# BW1098OBC_USB.net
KiCad netlist of a schematic drawn in Altium Designer
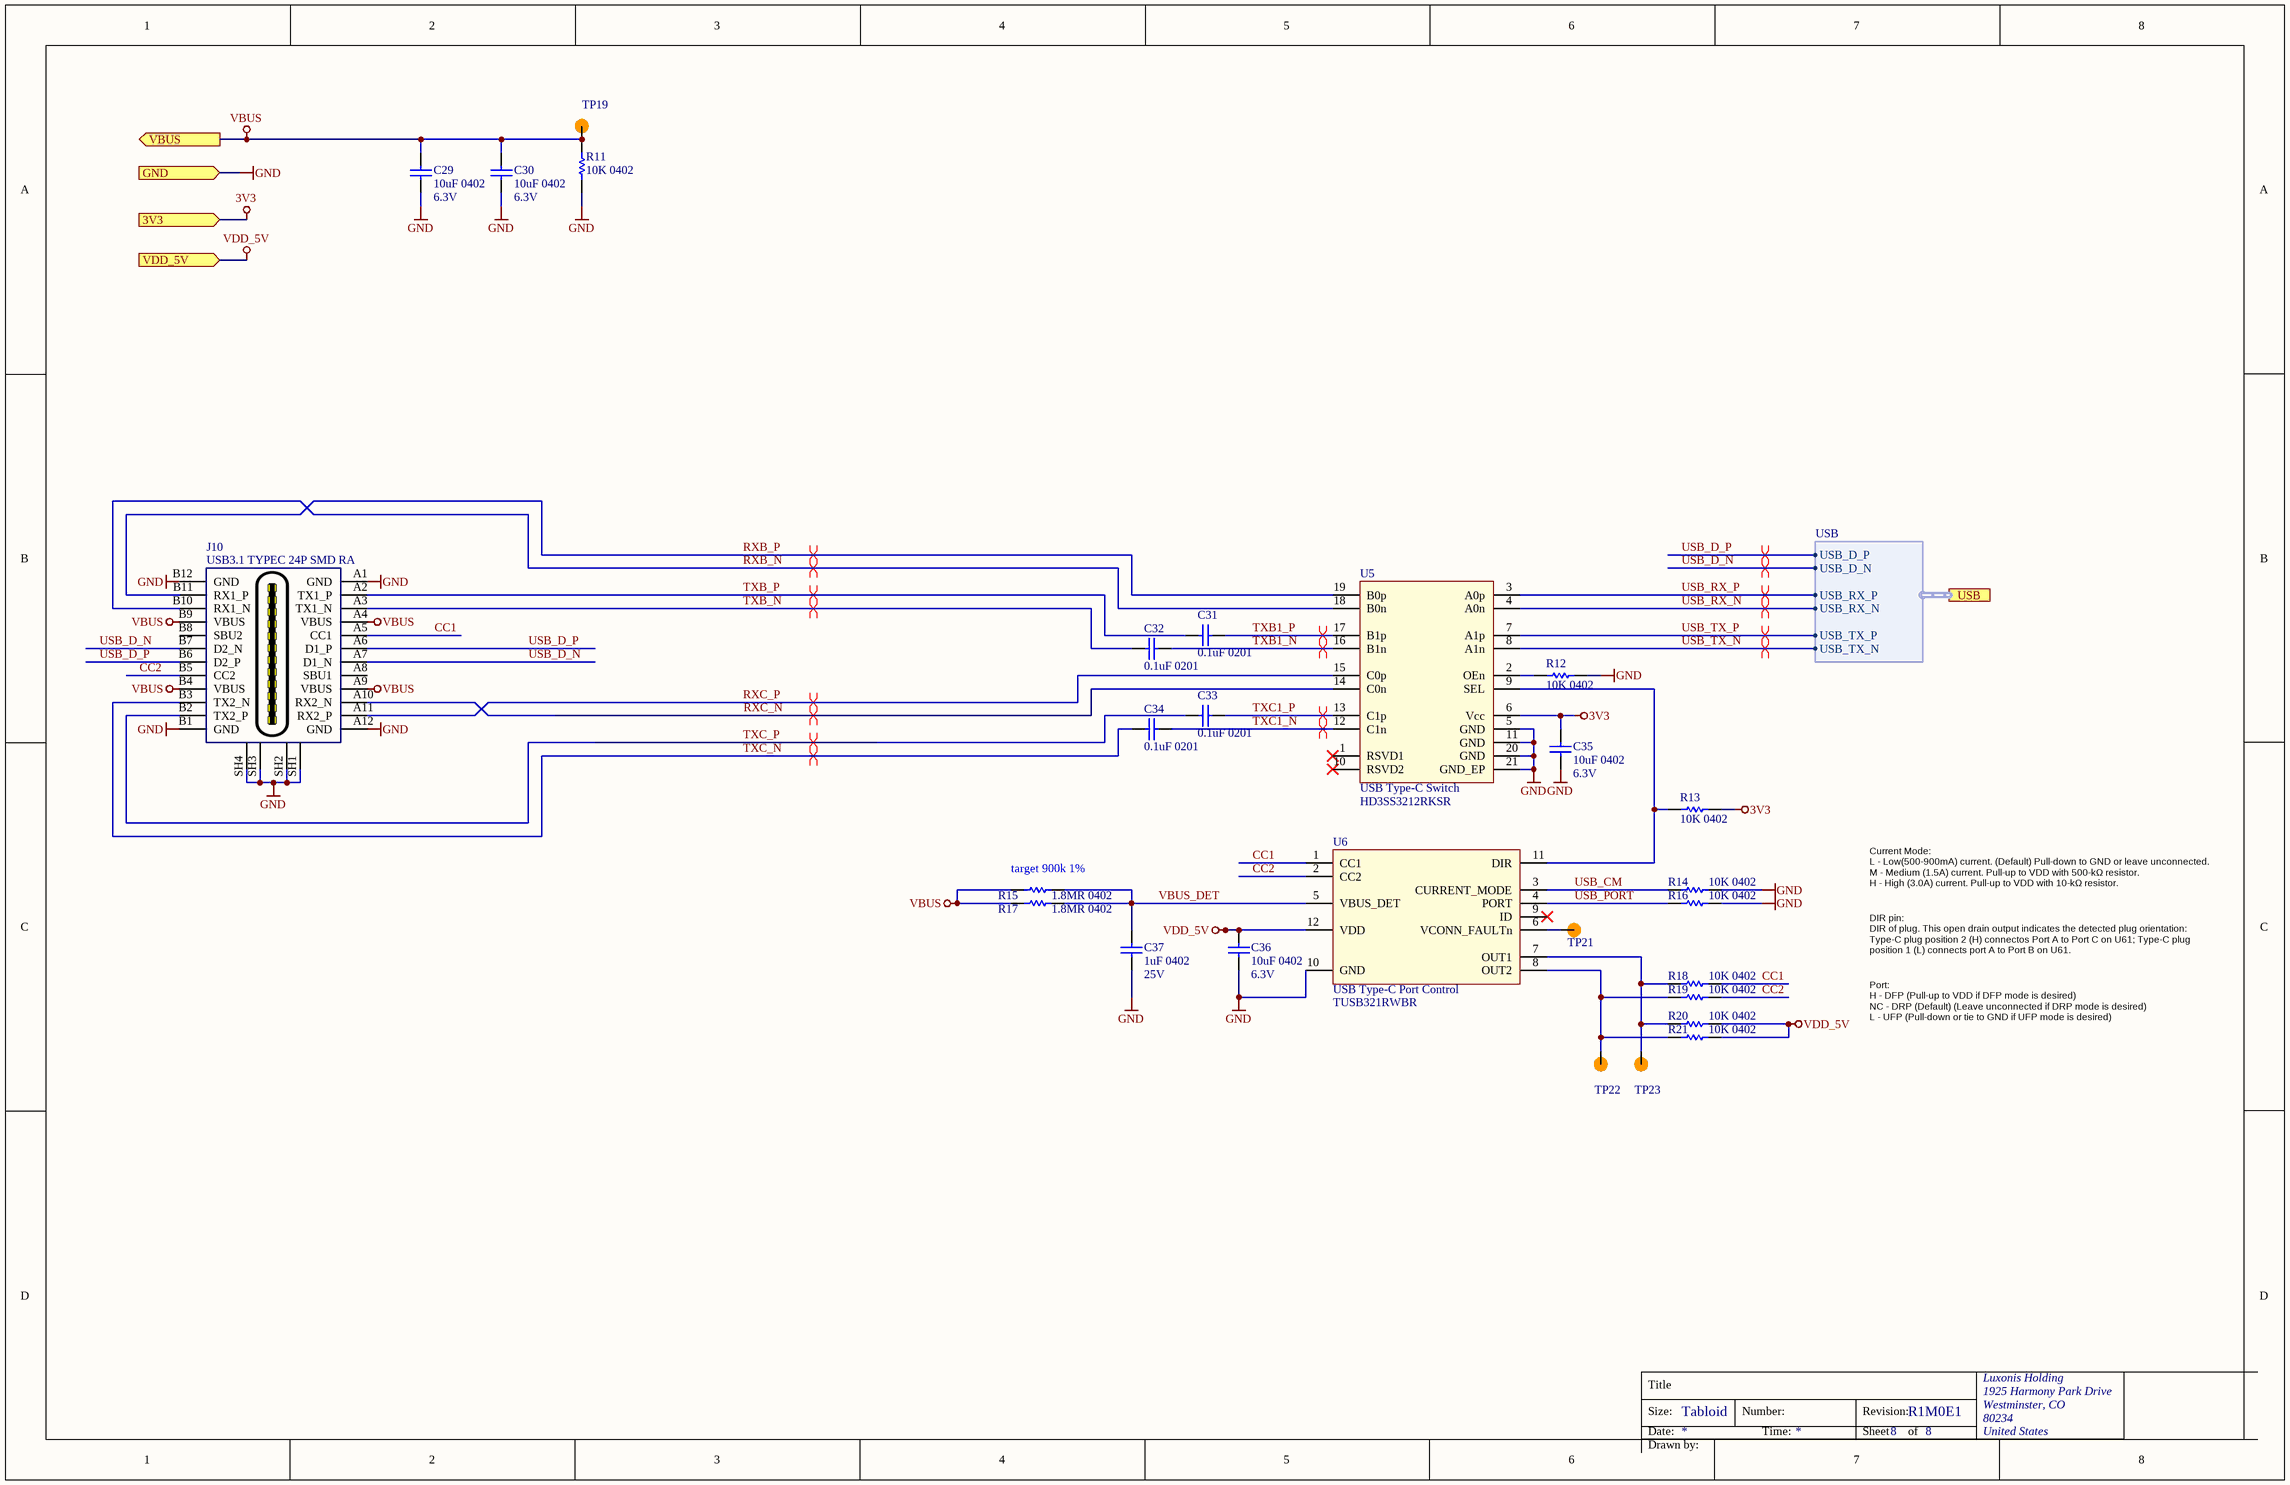
[diagram p0: BW1098OBC_USB.SchDoc]

(export (version "E")
  (design (tool "Eeschema 10.0.6"))
  (components
    (comp (ref "C29")
      (value "10uF 0402")
      (footprint "CAP_Altium_Vault_Generic:CAPC0402(1005)70_L")
      (description "CAP CER 10UF 6.3V X5R 0402 20%")
      (fields (field (name "TOLERANCE") "20%") (field (name "VOLTAGE RATING") "6.3V"))
      (libsource (lib "LuxonisMaster") (part "GRM155R60J106ME15D"))
    )
    (comp (ref "C30")
      (value "10uF 0402")
      (footprint "CAP_Altium_Vault_Generic:CAPC0402(1005)70_L")
      (description "CAP CER 10UF 6.3V X5R 0402 20%")
      (fields (field (name "TOLERANCE") "20%") (field (name "VOLTAGE RATING") "6.3V"))
      (libsource (lib "LuxonisMaster") (part "GRM155R60J106ME15D"))
    )
    (comp (ref "C31")
      (value "0.1uF 0201")
      (footprint "CAP_Altium_Vault_Generic:CAPC0201(0603)33_L")
      (description "CAP CER 0.1UF 10V X5R 0201")
      (fields (field (name "TOLERANCE") "10%") (field (name "VOLTAGE") "10V"))
      (libsource (lib "LuxonisMaster") (part "GRM033R61A104KE15D"))
    )
    (comp (ref "C32")
      (value "0.1uF 0201")
      (footprint "CAP_Altium_Vault_Generic:CAPC0201(0603)33_L")
      (description "CAP CER 0.1UF 10V X5R 0201")
      (fields (field (name "TOLERANCE") "10%") (field (name "VOLTAGE") "10V"))
      (libsource (lib "LuxonisMaster") (part "GRM033R61A104KE15D"))
    )
    (comp (ref "C33")
      (value "0.1uF 0201")
      (footprint "CAP_Altium_Vault_Generic:CAPC0201(0603)33_L")
      (description "CAP CER 0.1UF 10V X5R 0201")
      (fields (field (name "TOLERANCE") "10%") (field (name "VOLTAGE") "10V"))
      (libsource (lib "LuxonisMaster") (part "GRM033R61A104KE15D"))
    )
    (comp (ref "C34")
      (value "0.1uF 0201")
      (footprint "CAP_Altium_Vault_Generic:CAPC0201(0603)33_L")
      (description "CAP CER 0.1UF 10V X5R 0201")
      (fields (field (name "TOLERANCE") "10%") (field (name "VOLTAGE") "10V"))
      (libsource (lib "LuxonisMaster") (part "GRM033R61A104KE15D"))
    )
    (comp (ref "C35")
      (value "10uF 0402")
      (footprint "CAP_Altium_Vault_Generic:CAPC0402(1005)70_L")
      (description "CAP CER 10UF 6.3V X5R 0402 20%")
      (fields (field (name "TOLERANCE") "20%") (field (name "VOLTAGE RATING") "6.3V"))
      (libsource (lib "LuxonisMaster") (part "GRM155R60J106ME15D"))
    )
    (comp (ref "C36")
      (value "10uF 0402")
      (footprint "CAP_Altium_Vault_Generic:CAPC0402(1005)70_L")
      (description "CAP CER 10UF 6.3V X5R 0402 20%")
      (fields (field (name "TOLERANCE") "20%") (field (name "VOLTAGE RATING") "6.3V"))
      (libsource (lib "LuxonisMaster") (part "GRM155R60J106ME15D"))
    )
    (comp (ref "C37")
      (value "1uF 0402")
      (footprint "CAP_Altium_Vault_Generic:CAPC0402(1005)70_N")
      (description "CAP CER 1UF 25V X5R 0402 10%")
      (fields
        (field (name "TOLERANCE") "10%")
        (field (name "VOLTAGE") "25V")
        (field (name "VOLTAGE RATING") "25V")
      )
      (libsource (lib "LuxonisMaster") (part "GRM155R61E105KA12D"))
    )
    (comp (ref "J10")
      (value "USB3.1 TYPEC 24P SMD RA")
      (footprint "LuxonisMaster:105450-0101")
      (description "CONN RCP USB3.1 TYPEC 24P SMD RA")
      (libsource (lib "LuxonisMaster") (part "105450-0101"))
    )
    (comp (ref "R11")
      (value "10K 0402")
      (footprint "RES_Altium_Vault_Generic:RESC0402(1005)_L")
      (fields (field (name "TOLERANCE") "1%"))
      (libsource (lib "LuxonisMaster") (part "RC0402FR-1310KL"))
    )
    (comp (ref "R12")
      (value "10K 0402")
      (footprint "RES_Altium_Vault_Generic:RESC0402(1005)_L")
      (fields (field (name "TOLERANCE") "1%"))
      (libsource (lib "LuxonisMaster") (part "RC0402FR-1310KL"))
    )
    (comp (ref "R13")
      (value "10K 0402")
      (footprint "RES_Altium_Vault_Generic:RESC0402(1005)_L")
      (fields (field (name "TOLERANCE") "1%"))
      (libsource (lib "LuxonisMaster") (part "RC0402FR-1310KL"))
    )
    (comp (ref "R14")
      (value "10K 0402")
      (footprint "RES_Altium_Vault_Generic:RESC0402(1005)_L")
      (fields (field (name "TOLERANCE") "1%"))
      (libsource (lib "LuxonisMaster") (part "RC0402FR-1310KL"))
    )
    (comp (ref "R15")
      (value "1.8MR 0402")
      (footprint "RES_Altium_Vault_Generic:RESC0402(1005)_L")
      (description "RES SMD 1.8M OHM 1% 1/16W 0402")
      (fields (field (name "TOLERANCE") "1%"))
      (libsource (lib "LuxonisMaster") (part "CRCW04021M80FKED"))
    )
    (comp (ref "R16")
      (value "10K 0402")
      (footprint "RES_Altium_Vault_Generic:RESC0402(1005)_L")
      (fields (field (name "TOLERANCE") "1%"))
      (libsource (lib "LuxonisMaster") (part "RC0402FR-1310KL"))
    )
    (comp (ref "R17")
      (value "1.8MR 0402")
      (footprint "RES_Altium_Vault_Generic:RESC0402(1005)_L")
      (description "RES SMD 1.8M OHM 1% 1/16W 0402")
      (fields (field (name "TOLERANCE") "1%"))
      (libsource (lib "LuxonisMaster") (part "CRCW04021M80FKED"))
    )
    (comp (ref "R18")
      (value "10K 0402")
      (footprint "RES_Altium_Vault_Generic:RESC0402(1005)_L")
      (fields (field (name "TOLERANCE") "1%"))
      (libsource (lib "LuxonisMaster") (part "RC0402FR-1310KL"))
    )
    (comp (ref "R19")
      (value "10K 0402")
      (footprint "RES_Altium_Vault_Generic:RESC0402(1005)_L")
      (fields (field (name "TOLERANCE") "1%"))
      (libsource (lib "LuxonisMaster") (part "RC0402FR-1310KL"))
    )
    (comp (ref "R20")
      (value "10K 0402")
      (footprint "RES_Altium_Vault_Generic:RESC0402(1005)_L")
      (fields (field (name "TOLERANCE") "1%"))
      (libsource (lib "LuxonisMaster") (part "RC0402FR-1310KL"))
    )
    (comp (ref "R21")
      (value "10K 0402")
      (footprint "RES_Altium_Vault_Generic:RESC0402(1005)_L")
      (fields (field (name "TOLERANCE") "1%"))
      (libsource (lib "LuxonisMaster") (part "RC0402FR-1310KL"))
    )
    (comp (ref "TP19")
      (value "TP100_200_NS")
      (footprint "LuxonisMaster:TP100_200_NS")
      (libsource (lib "LuxonisMaster") (part "TEST_POINT"))
    )
    (comp (ref "TP21")
      (value "TP100_200_NS")
      (footprint "LuxonisMaster:TP100_200_NS")
      (libsource (lib "LuxonisMaster") (part "TEST_POINT"))
    )
    (comp (ref "TP22")
      (value "TP100_200_NS")
      (footprint "LuxonisMaster:TP100_200_NS")
      (libsource (lib "LuxonisMaster") (part "TEST_POINT"))
    )
    (comp (ref "TP23")
      (value "TP100_200_NS")
      (footprint "LuxonisMaster:TP100_200_NS")
      (libsource (lib "LuxonisMaster") (part "TEST_POINT"))
    )
    (comp (ref "U5")
      (value "USB Type-C Switch")
      (footprint "LuxonisMaster:HD3SS3212RKSR")
      (description "IC MUX 2:1 8 OHM 20VQFN")
      (fields (field (name "MANUFACTURER PART NUMBER 1") "HD3SS3212RKSR"))
      (libsource (lib "LuxonisMaster") (part "HD3SS3212RKSR"))
    )
    (comp (ref "U6")
      (value "USB Type-C Port Control")
      (footprint "LuxonisMaster:TUSB321RWBR")
      (description "IC USB PORT CONTROL TYPE-C 12X2Q")
      (fields (field (name "MANUFACTURER PART NUMBER 1") "TUSB321RWBR"))
      (libsource (lib "LuxonisMaster") (part "TUSB321RWBR"))
    )
  )
  (nets
    (net (code "2") (name "/CC1") (class "Default")
      (node (ref "J10") (pin "A5") (pinfunction "CC1_A5") (pintype "passive"))
      (node (ref "R18") (pin "2") (pinfunction "2_2") (pintype "passive"))
      (node (ref "U6") (pin "1") (pinfunction "CC1_1") (pintype "passive"))
    )
    (net (code "3") (name "/CC2") (class "Default")
      (node (ref "J10") (pin "B5") (pinfunction "CC2_B5") (pintype "passive"))
      (node (ref "R19") (pin "2") (pinfunction "2_2") (pintype "passive"))
      (node (ref "U6") (pin "2") (pinfunction "CC2_2") (pintype "passive"))
    )
    (net (code "4") (name "/RXB_N") (class "Default")
      (node (ref "J10") (pin "B10") (pinfunction "RX1_N_B10") (pintype "passive"))
      (node (ref "U5") (pin "18") (pinfunction "B0n_18") (pintype "passive"))
    )
    (net (code "5") (name "/RXB_P") (class "Default")
      (node (ref "J10") (pin "B11") (pinfunction "RX1_P_B11") (pintype "passive"))
      (node (ref "U5") (pin "19") (pinfunction "B0p_19") (pintype "passive"))
    )
    (net (code "6") (name "/RXC_N") (class "Default")
      (node (ref "J10") (pin "A10") (pinfunction "RX2_N_A10") (pintype "passive"))
      (node (ref "U5") (pin "14") (pinfunction "C0n_14") (pintype "passive"))
    )
    (net (code "7") (name "/RXC_P") (class "Default")
      (node (ref "J10") (pin "A11") (pinfunction "RX2_P_A11") (pintype "passive"))
      (node (ref "U5") (pin "15") (pinfunction "C0p_15") (pintype "passive"))
    )
    (net (code "8") (name "/TXB1_N") (class "Default")
      (node (ref "C32") (pin "2") (pinfunction "2_2") (pintype "passive"))
      (node (ref "U5") (pin "16") (pinfunction "B1n_16") (pintype "passive"))
    )
    (net (code "9") (name "/TXB1_P") (class "Default")
      (node (ref "C31") (pin "2") (pinfunction "2_2") (pintype "passive"))
      (node (ref "U5") (pin "17") (pinfunction "B1p_17") (pintype "passive"))
    )
    (net (code "10") (name "/TXB_N") (class "Default")
      (node (ref "C32") (pin "1") (pinfunction "1_1") (pintype "passive"))
      (node (ref "J10") (pin "A3") (pinfunction "TX1_N_A3") (pintype "passive"))
    )
    (net (code "11") (name "/TXB_P") (class "Default")
      (node (ref "C31") (pin "1") (pinfunction "1_1") (pintype "passive"))
      (node (ref "J10") (pin "A2") (pinfunction "TX1_P_A2") (pintype "passive"))
    )
    (net (code "12") (name "/TXC1_N") (class "Default")
      (node (ref "C34") (pin "2") (pinfunction "2_2") (pintype "passive"))
      (node (ref "U5") (pin "12") (pinfunction "C1n_12") (pintype "passive"))
    )
    (net (code "13") (name "/TXC1_P") (class "Default")
      (node (ref "C33") (pin "2") (pinfunction "2_2") (pintype "passive"))
      (node (ref "U5") (pin "13") (pinfunction "C1p_13") (pintype "passive"))
    )
    (net (code "14") (name "/TXC_N") (class "Default")
      (node (ref "C34") (pin "1") (pinfunction "1_1") (pintype "passive"))
      (node (ref "J10") (pin "B3") (pinfunction "TX2_N_B3") (pintype "passive"))
    )
    (net (code "15") (name "/TXC_P") (class "Default")
      (node (ref "C33") (pin "1") (pinfunction "1_1") (pintype "passive"))
      (node (ref "J10") (pin "B2") (pinfunction "TX2_P_B2") (pintype "passive"))
    )
    (net (code "16") (name "/USB_CM") (class "Default")
      (node (ref "R14") (pin "1") (pinfunction "1_1") (pintype "passive"))
      (node (ref "U6") (pin "3") (pinfunction "CURRENT_MODE_3") (pintype "passive"))
    )
    (net (code "17") (name "/USB_D_N") (class "Default")
      (node (ref "J10") (pin "A7") (pinfunction "D1_N_A7") (pintype "passive"))
      (node (ref "J10") (pin "B7") (pinfunction "D2_N_B7") (pintype "passive"))
    )
    (net (code "18") (name "/USB_D_P") (class "Default")
      (node (ref "J10") (pin "A6") (pinfunction "D1_P_A6") (pintype "passive"))
      (node (ref "J10") (pin "B6") (pinfunction "D2_P_B6") (pintype "passive"))
    )
    (net (code "19") (name "/USB_PORT") (class "Default")
      (node (ref "R16") (pin "1") (pinfunction "1_1") (pintype "passive"))
      (node (ref "U6") (pin "4") (pinfunction "PORT_4") (pintype "passive"))
    )
    (net (code "20") (name "/USB_RX_N") (class "Default")
      (node (ref "U5") (pin "4") (pinfunction "A0n_4") (pintype "passive"))
    )
    (net (code "21") (name "/USB_RX_P") (class "Default")
      (node (ref "U5") (pin "3") (pinfunction "A0p_3") (pintype "passive"))
    )
    (net (code "22") (name "/USB_TX_N") (class "Default")
      (node (ref "U5") (pin "8") (pinfunction "A1n_8") (pintype "passive"))
    )
    (net (code "23") (name "/USB_TX_P") (class "Default")
      (node (ref "U5") (pin "7") (pinfunction "A1p_7") (pintype "passive"))
    )
    (net (code "24") (name "/VBUS_DET") (class "Default")
      (node (ref "C37") (pin "2") (pinfunction "2_2") (pintype "passive"))
      (node (ref "R15") (pin "2") (pinfunction "2_2") (pintype "passive"))
      (node (ref "R17") (pin "2") (pinfunction "2_2") (pintype "passive"))
      (node (ref "U6") (pin "5") (pinfunction "VBUS_DET_5") (pintype "passive"))
    )
    (net (code "26") (name "3V3") (class "Default")
      (node (ref "C35") (pin "2") (pinfunction "2_2") (pintype "passive"))
      (node (ref "R13") (pin "2") (pinfunction "2_2") (pintype "passive"))
      (node (ref "U5") (pin "6") (pinfunction "Vcc_6") (pintype "passive"))
    )
    (net (code "27") (name "GND") (class "Default")
      (node (ref "C29") (pin "1") (pinfunction "1_1") (pintype "passive"))
      (node (ref "C30") (pin "1") (pinfunction "1_1") (pintype "passive"))
      (node (ref "C35") (pin "1") (pinfunction "1_1") (pintype "passive"))
      (node (ref "C36") (pin "1") (pinfunction "1_1") (pintype "passive"))
      (node (ref "C37") (pin "1") (pinfunction "1_1") (pintype "passive"))
      (node (ref "J10") (pin "A1") (pinfunction "GND_A1") (pintype "passive"))
      (node (ref "J10") (pin "A12") (pinfunction "GND_A12") (pintype "passive"))
      (node (ref "J10") (pin "B1") (pinfunction "GND_B1") (pintype "passive"))
      (node (ref "J10") (pin "B12") (pinfunction "GND_B12") (pintype "passive"))
      (node (ref "J10") (pin "SH1") (pinfunction "SH_SH1") (pintype "passive"))
      (node (ref "J10") (pin "SH2") (pinfunction "SH_SH2") (pintype "passive"))
      (node (ref "J10") (pin "SH3") (pinfunction "SH_SH3") (pintype "passive"))
      (node (ref "J10") (pin "SH4") (pinfunction "SH_SH4") (pintype "passive"))
      (node (ref "R11") (pin "1") (pinfunction "1_1") (pintype "passive"))
      (node (ref "R12") (pin "2") (pinfunction "2_2") (pintype "passive"))
      (node (ref "R14") (pin "2") (pinfunction "2_2") (pintype "passive"))
      (node (ref "R16") (pin "2") (pinfunction "2_2") (pintype "passive"))
      (node (ref "U5") (pin "11") (pinfunction "GND_11") (pintype "passive"))
      (node (ref "U5") (pin "20") (pinfunction "GND_20") (pintype "passive"))
      (node (ref "U5") (pin "21") (pinfunction "GND_EP_21") (pintype "passive"))
      (node (ref "U5") (pin "5") (pinfunction "GND_5") (pintype "passive"))
      (node (ref "U6") (pin "10") (pinfunction "GND_10") (pintype "passive"))
    )
    (net (code "28") (name "Net-(U5-OEn)") (class "Default")
      (node (ref "R12") (pin "1") (pinfunction "1_1") (pintype "passive"))
      (node (ref "U5") (pin "2") (pinfunction "OEn_2") (pintype "passive"))
    )
    (net (code "29") (name "Net-(U5-SEL)") (class "Default")
      (node (ref "R13") (pin "1") (pinfunction "1_1") (pintype "passive"))
      (node (ref "U5") (pin "9") (pinfunction "SEL_9") (pintype "passive"))
      (node (ref "U6") (pin "11") (pinfunction "DIR_11") (pintype "passive"))
    )
    (net (code "30") (name "Net-(U6-OUT1)") (class "Default")
      (node (ref "R18") (pin "1") (pinfunction "1_1") (pintype "passive"))
      (node (ref "R20") (pin "1") (pinfunction "1_1") (pintype "passive"))
      (node (ref "TP23") (pin "1") (pintype "passive"))
      (node (ref "U6") (pin "7") (pinfunction "OUT1_7") (pintype "passive"))
    )
    (net (code "31") (name "Net-(U6-OUT2)") (class "Default")
      (node (ref "R19") (pin "1") (pinfunction "1_1") (pintype "passive"))
      (node (ref "R21") (pin "1") (pinfunction "1_1") (pintype "passive"))
      (node (ref "TP22") (pin "1") (pintype "passive"))
      (node (ref "U6") (pin "8") (pinfunction "OUT2_8") (pintype "passive"))
    )
    (net (code "32") (name "Net-(U6-VCONN_FAULTn)") (class "Default")
      (node (ref "TP21") (pin "1") (pintype "passive"))
      (node (ref "U6") (pin "6") (pinfunction "VCONN_FAULTn_6") (pintype "passive"))
    )
    (net (code "33") (name "VBUS") (class "Default")
      (node (ref "C29") (pin "2") (pinfunction "2_2") (pintype "passive"))
      (node (ref "C30") (pin "2") (pinfunction "2_2") (pintype "passive"))
      (node (ref "J10") (pin "A4") (pinfunction "VBUS_A4") (pintype "passive"))
      (node (ref "J10") (pin "A9") (pinfunction "VBUS_A9") (pintype "passive"))
      (node (ref "J10") (pin "B4") (pinfunction "VBUS_B4") (pintype "passive"))
      (node (ref "J10") (pin "B9") (pinfunction "VBUS_B9") (pintype "passive"))
      (node (ref "R11") (pin "2") (pinfunction "2_2") (pintype "passive"))
      (node (ref "R15") (pin "1") (pinfunction "1_1") (pintype "passive"))
      (node (ref "R17") (pin "1") (pinfunction "1_1") (pintype "passive"))
      (node (ref "TP19") (pin "1") (pintype "passive"))
    )
    (net (code "34") (name "VDD_5V") (class "Default")
      (node (ref "C36") (pin "2") (pinfunction "2_2") (pintype "passive"))
      (node (ref "R20") (pin "2") (pinfunction "2_2") (pintype "passive"))
      (node (ref "R21") (pin "2") (pinfunction "2_2") (pintype "passive"))
      (node (ref "U6") (pin "12") (pinfunction "VDD_12") (pintype "passive"))
    )
    (net (code "35") (name "unconnected-(J10-SBU1-PadA8)") (class "Default")
      (node (ref "J10") (pin "A8") (pinfunction "SBU1_A8") (pintype "passive"))
    )
    (net (code "36") (name "unconnected-(J10-SBU2-PadB8)") (class "Default")
      (node (ref "J10") (pin "B8") (pinfunction "SBU2_B8") (pintype "passive"))
    )
    (net (code "37") (name "unconnected-(U5-RSVD1-Pad1)") (class "Default")
      (node (ref "U5") (pin "1") (pinfunction "RSVD1_1") (pintype "passive+no_connect"))
    )
    (net (code "38") (name "unconnected-(U5-RSVD2-Pad10)") (class "Default")
      (node (ref "U5") (pin "10") (pinfunction "RSVD2_10") (pintype "passive+no_connect"))
    )
    (net (code "39") (name "unconnected-(U6-ID-Pad9)") (class "Default")
      (node (ref "U6") (pin "9") (pinfunction "ID_9") (pintype "passive+no_connect"))
    )
  )
)
